# Eency_--_HM-10_v01.net
KiCad netlist of a schematic drawn in EAGLE
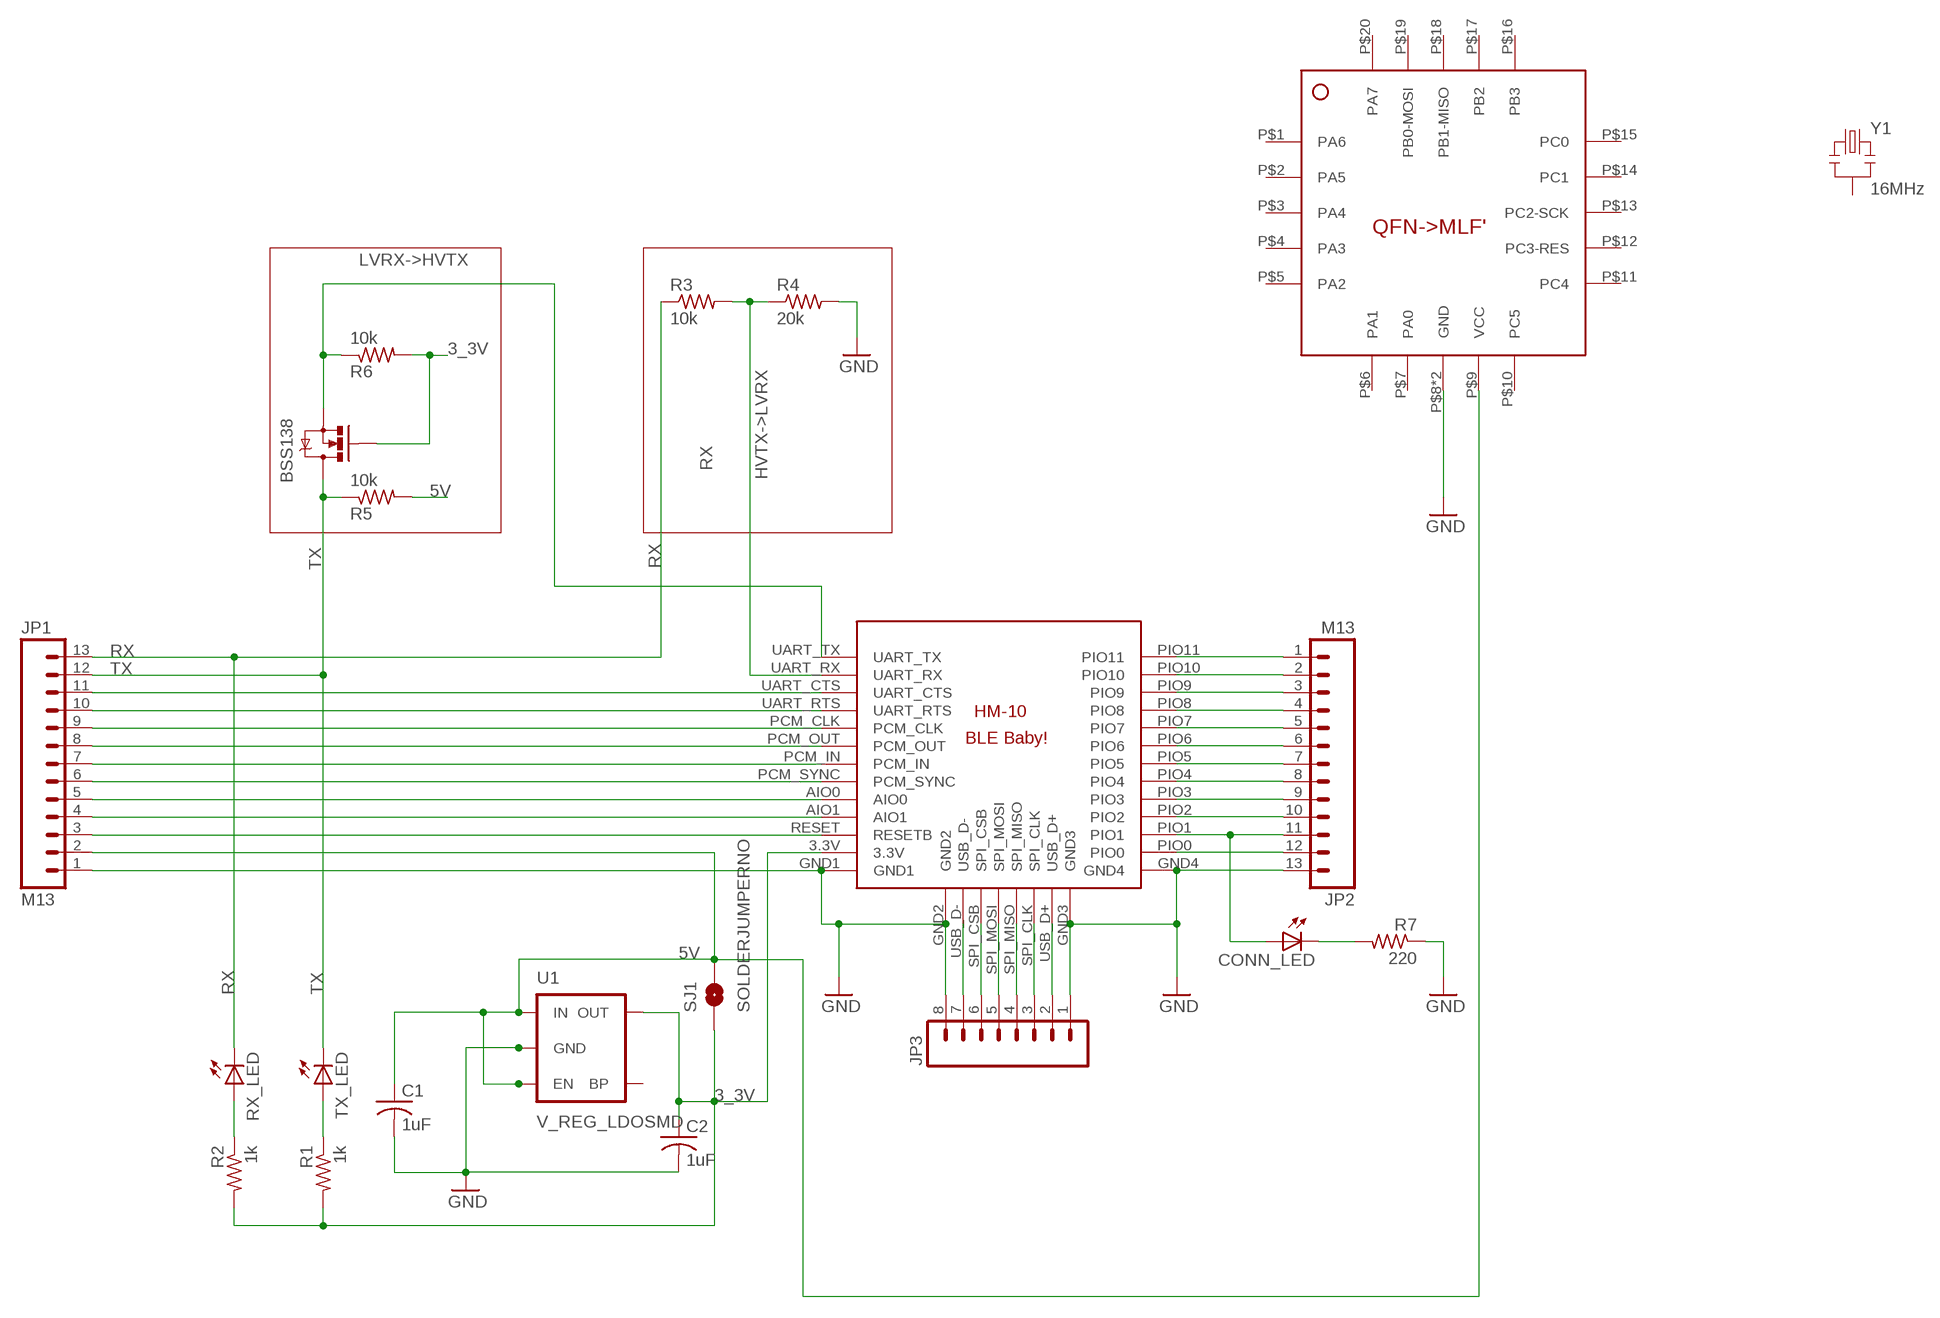
[diagram p0: schematic, sheet 1]

(export (version "E")
  (design (tool "Eeschema 10.0.6"))
  (components
    (comp (ref "BSS138")
      (value "MOSFET-NCHANNELSMD")
      (footprint "eagle-import:SOT23-3")
      (libsource (lib "eagle-import") (part "MOSFET-NCHANNELSMD"))
    )
    (comp (ref "C1")
      (value "1uF")
      (footprint "eagle-import:C0805K")
      (libsource (lib "eagle-import") (part "C-USC0805K"))
    )
    (comp (ref "C2")
      (value "1uF")
      (footprint "eagle-import:C0805K")
      (libsource (lib "eagle-import") (part "C-USC0805K"))
    )
    (comp (ref "CONN_LED")
      (value "LED0603")
      (footprint "eagle-import:LED-0603")
      (libsource (lib "eagle-import") (part "LED0603"))
    )
    (comp (ref "JP1")
      (value "M13")
      (footprint "eagle-import:1X13")
      (libsource (lib "eagle-import") (part "M13"))
    )
    (comp (ref "JP2")
      (value "M13")
      (footprint "eagle-import:1X13")
      (libsource (lib "eagle-import") (part "M13"))
    )
    (comp (ref "JP3")
      (value "M081X08")
      (footprint "eagle-import:1X08")
      (libsource (lib "eagle-import") (part "M081X08"))
    )
    (comp (ref "R1")
      (value "1k")
      (footprint "eagle-import:M0805")
      (libsource (lib "eagle-import") (part "R-US_M0805"))
    )
    (comp (ref "R2")
      (value "1k")
      (footprint "eagle-import:M0805")
      (libsource (lib "eagle-import") (part "R-US_M0805"))
    )
    (comp (ref "R3")
      (value "10k")
      (footprint "eagle-import:M0805")
      (libsource (lib "eagle-import") (part "R-US_M0805"))
    )
    (comp (ref "R4")
      (value "20k")
      (footprint "eagle-import:M0805")
      (libsource (lib "eagle-import") (part "R-US_M0805"))
    )
    (comp (ref "R5")
      (value "10k")
      (footprint "eagle-import:M0805")
      (libsource (lib "eagle-import") (part "R-US_M0805"))
    )
    (comp (ref "R6")
      (value "10k")
      (footprint "eagle-import:M0805")
      (libsource (lib "eagle-import") (part "R-US_M0805"))
    )
    (comp (ref "R7")
      (value "220")
      (footprint "eagle-import:M0805")
      (libsource (lib "eagle-import") (part "R-US_M0805"))
    )
    (comp (ref "RX_LED")
      (value "LED0603")
      (footprint "eagle-import:LED-0603")
      (libsource (lib "eagle-import") (part "LED0603"))
    )
    (comp (ref "SJ1")
      (value "SOLDERJUMPERNO")
      (footprint "eagle-import:SJ_2S-NO")
      (libsource (lib "eagle-import") (part "SOLDERJUMPERNO"))
    )
    (comp (ref "TX_LED")
      (value "LED0603")
      (footprint "eagle-import:LED-0603")
      (libsource (lib "eagle-import") (part "LED0603"))
    )
    (comp (ref "U$1")
      (value "BLE-HM-10")
      (footprint "eagle-import:BLE-HM-10")
      (libsource (lib "eagle-import") (part "BLE-HM-10"))
    )
    (comp (ref "U$4")
      (value "AVR-5_ATTINY1634")
      (footprint "eagle-import:AVR-5_MLF20_ATTINY13")
      (libsource (lib "eagle-import") (part "AVR-5_ATTINY1634"))
    )
    (comp (ref "U1")
      (value "V_REG_LDOSMD")
      (footprint "eagle-import:SOT23-5")
      (libsource (lib "eagle-import") (part "V_REG_LDOSMD"))
    )
    (comp (ref "Y1")
      (value "16MHz")
      (footprint "eagle-import:RESONATOR-SMD")
      (libsource (lib "eagle-import") (part "RESONATOR16MHZ"))
    )
  )
  (nets
    (net (code "1") (name "/3_3V") (class "Default")
      (node (ref "BSS138") (pin "1") (pinfunction "G_1") (pintype "passive"))
      (node (ref "C2") (pin "1") (pinfunction "1_1") (pintype "passive"))
      (node (ref "R1") (pin "2") (pinfunction "2_2") (pintype "passive"))
      (node (ref "R2") (pin "2") (pinfunction "2_2") (pintype "passive"))
      (node (ref "R6") (pin "2") (pinfunction "2_2") (pintype "passive"))
      (node (ref "SJ1") (pin "1") (pinfunction "1_1") (pintype "passive"))
      (node (ref "U$1") (pin "3.3V") (pinfunction "3.3V_3.3V") (pintype "bidirectional"))
      (node (ref "U1") (pin "5") (pinfunction "OUT_5") (pintype "passive"))
    )
    (net (code "2") (name "/5V") (class "Default")
      (node (ref "C1") (pin "1") (pinfunction "1_1") (pintype "passive"))
      (node (ref "JP1") (pin "2") (pinfunction "2_2") (pintype "passive"))
      (node (ref "R5") (pin "2") (pinfunction "2_2") (pintype "passive"))
      (node (ref "SJ1") (pin "2") (pinfunction "2_2") (pintype "passive"))
      (node (ref "U$4") (pin "P$9") (pinfunction "VCC_P$9") (pintype "bidirectional"))
      (node (ref "U1") (pin "1") (pinfunction "IN_1") (pintype "input"))
      (node (ref "U1") (pin "3") (pinfunction "EN_3") (pintype "input"))
    )
    (net (code "3") (name "/HVTX->LVRX") (class "Default")
      (node (ref "R3") (pin "2") (pinfunction "2_2") (pintype "passive"))
      (node (ref "R4") (pin "1") (pinfunction "1_1") (pintype "passive"))
      (node (ref "U$1") (pin "UART_RX") (pinfunction "UART_RX_UART_RX") (pintype "bidirectional"))
    )
    (net (code "4") (name "/LVRX->HVTX") (class "Default")
      (node (ref "BSS138") (pin "2") (pinfunction "S_2") (pintype "passive"))
      (node (ref "R6") (pin "1") (pinfunction "1_1") (pintype "passive"))
      (node (ref "U$1") (pin "UART_TX") (pinfunction "UART_TX_UART_TX") (pintype "bidirectional"))
    )
    (net (code "5") (name "/RX") (class "Default")
      (node (ref "JP1") (pin "13") (pinfunction "13_13") (pintype "passive"))
      (node (ref "R3") (pin "1") (pinfunction "1_1") (pintype "passive"))
      (node (ref "RX_LED") (pin "C") (pinfunction "C_C") (pintype "passive"))
    )
    (net (code "6") (name "/TX") (class "Default")
      (node (ref "BSS138") (pin "3") (pinfunction "D_3") (pintype "passive"))
      (node (ref "JP1") (pin "12") (pinfunction "12_12") (pintype "passive"))
      (node (ref "R5") (pin "1") (pinfunction "1_1") (pintype "passive"))
      (node (ref "TX_LED") (pin "C") (pinfunction "C_C") (pintype "passive"))
    )
    (net (code "7") (name "GND") (class "Default")
      (node (ref "C1") (pin "2") (pinfunction "2_2") (pintype "passive"))
      (node (ref "C2") (pin "2") (pinfunction "2_2") (pintype "passive"))
      (node (ref "JP1") (pin "1") (pinfunction "1_1") (pintype "passive"))
      (node (ref "JP2") (pin "13") (pinfunction "13_13") (pintype "passive"))
      (node (ref "JP3") (pin "1") (pinfunction "1_1") (pintype "passive"))
      (node (ref "JP3") (pin "8") (pinfunction "8_8") (pintype "passive"))
      (node (ref "R4") (pin "2") (pinfunction "2_2") (pintype "passive"))
      (node (ref "R7") (pin "1") (pinfunction "1_1") (pintype "passive"))
      (node (ref "U$1") (pin "GND1") (pinfunction "GND1_GND1") (pintype "bidirectional"))
      (node (ref "U$1") (pin "GND2") (pinfunction "GND2_GND2") (pintype "bidirectional"))
      (node (ref "U$1") (pin "GND3") (pinfunction "GND3_GND3") (pintype "bidirectional"))
      (node (ref "U$1") (pin "GND4") (pinfunction "GND4_GND4") (pintype "bidirectional"))
      (node (ref "U$4") (pin "P$21") (pinfunction "GND_P$21") (pintype "bidirectional"))
      (node (ref "U$4") (pin "P$8") (pinfunction "GND_P$8") (pintype "bidirectional"))
      (node (ref "U1") (pin "2") (pinfunction "GND_2") (pintype "input"))
    )
    (net (code "8") (name "Net-(CONN_LED-PadA)") (class "Default")
      (node (ref "CONN_LED") (pin "A") (pinfunction "A_A") (pintype "passive"))
      (node (ref "JP2") (pin "11") (pinfunction "11_11") (pintype "passive"))
      (node (ref "U$1") (pin "PIO1") (pinfunction "PIO1_PIO1") (pintype "bidirectional"))
    )
    (net (code "9") (name "Net-(CONN_LED-PadC)") (class "Default")
      (node (ref "CONN_LED") (pin "C") (pinfunction "C_C") (pintype "passive"))
      (node (ref "R7") (pin "2") (pinfunction "2_2") (pintype "passive"))
    )
    (net (code "10") (name "Net-(JP1-Pad4)") (class "Default")
      (node (ref "JP1") (pin "4") (pinfunction "4_4") (pintype "passive"))
      (node (ref "U$1") (pin "AIO1") (pinfunction "AIO1_AIO1") (pintype "bidirectional"))
    )
    (net (code "11") (name "Net-(JP1-Pad5)") (class "Default")
      (node (ref "JP1") (pin "5") (pinfunction "5_5") (pintype "passive"))
      (node (ref "U$1") (pin "AIO0") (pinfunction "AIO0_AIO0") (pintype "bidirectional"))
    )
    (net (code "12") (name "Net-(JP1-Pad6)") (class "Default")
      (node (ref "JP1") (pin "6") (pinfunction "6_6") (pintype "passive"))
      (node (ref "U$1") (pin "PCM_SYNC") (pinfunction "PCM_SYNC_PCM_SYNC") (pintype "bidirectional"))
    )
    (net (code "13") (name "Net-(JP1-Pad7)") (class "Default")
      (node (ref "JP1") (pin "7") (pinfunction "7_7") (pintype "passive"))
      (node (ref "U$1") (pin "PCM_IN") (pinfunction "PCM_IN_PCM_IN") (pintype "bidirectional"))
    )
    (net (code "14") (name "Net-(JP1-Pad8)") (class "Default")
      (node (ref "JP1") (pin "8") (pinfunction "8_8") (pintype "passive"))
      (node (ref "U$1") (pin "PCM_OUT") (pinfunction "PCM_OUT_PCM_OUT") (pintype "bidirectional"))
    )
    (net (code "15") (name "Net-(JP1-Pad9)") (class "Default")
      (node (ref "JP1") (pin "9") (pinfunction "9_9") (pintype "passive"))
      (node (ref "U$1") (pin "PCM_CLK") (pinfunction "PCM_CLK_PCM_CLK") (pintype "bidirectional"))
    )
    (net (code "16") (name "Net-(JP1-Pad10)") (class "Default")
      (node (ref "JP1") (pin "10") (pinfunction "10_10") (pintype "passive"))
      (node (ref "U$1") (pin "UART_RTS") (pinfunction "UART_RTS_UART_RTS") (pintype "bidirectional"))
    )
    (net (code "17") (name "Net-(JP1-Pad11)") (class "Default")
      (node (ref "JP1") (pin "11") (pinfunction "11_11") (pintype "passive"))
      (node (ref "U$1") (pin "UART_CTS") (pinfunction "UART_CTS_UART_CTS") (pintype "bidirectional"))
    )
    (net (code "18") (name "Net-(JP2-Pad1)") (class "Default")
      (node (ref "JP2") (pin "1") (pinfunction "1_1") (pintype "passive"))
      (node (ref "U$1") (pin "PIO11") (pinfunction "PIO11_PIO11") (pintype "bidirectional"))
    )
    (net (code "19") (name "Net-(JP2-Pad2)") (class "Default")
      (node (ref "JP2") (pin "2") (pinfunction "2_2") (pintype "passive"))
      (node (ref "U$1") (pin "PIO10") (pinfunction "PIO10_PIO10") (pintype "bidirectional"))
    )
    (net (code "20") (name "Net-(JP2-Pad3)") (class "Default")
      (node (ref "JP2") (pin "3") (pinfunction "3_3") (pintype "passive"))
      (node (ref "U$1") (pin "PIO9") (pinfunction "PIO9_PIO9") (pintype "bidirectional"))
    )
    (net (code "21") (name "Net-(JP2-Pad4)") (class "Default")
      (node (ref "JP2") (pin "4") (pinfunction "4_4") (pintype "passive"))
      (node (ref "U$1") (pin "PIO8") (pinfunction "PIO8_PIO8") (pintype "bidirectional"))
    )
    (net (code "22") (name "Net-(JP2-Pad5)") (class "Default")
      (node (ref "JP2") (pin "5") (pinfunction "5_5") (pintype "passive"))
      (node (ref "U$1") (pin "PIO7") (pinfunction "PIO7_PIO7") (pintype "bidirectional"))
    )
    (net (code "23") (name "Net-(JP2-Pad6)") (class "Default")
      (node (ref "JP2") (pin "6") (pinfunction "6_6") (pintype "passive"))
      (node (ref "U$1") (pin "PIO6") (pinfunction "PIO6_PIO6") (pintype "bidirectional"))
    )
    (net (code "24") (name "Net-(JP2-Pad7)") (class "Default")
      (node (ref "JP2") (pin "7") (pinfunction "7_7") (pintype "passive"))
      (node (ref "U$1") (pin "PIO5") (pinfunction "PIO5_PIO5") (pintype "bidirectional"))
    )
    (net (code "25") (name "Net-(JP2-Pad8)") (class "Default")
      (node (ref "JP2") (pin "8") (pinfunction "8_8") (pintype "passive"))
      (node (ref "U$1") (pin "PIO4") (pinfunction "PIO4_PIO4") (pintype "bidirectional"))
    )
    (net (code "26") (name "Net-(JP2-Pad9)") (class "Default")
      (node (ref "JP2") (pin "9") (pinfunction "9_9") (pintype "passive"))
      (node (ref "U$1") (pin "PIO3") (pinfunction "PIO3_PIO3") (pintype "bidirectional"))
    )
    (net (code "27") (name "Net-(JP2-Pad10)") (class "Default")
      (node (ref "JP2") (pin "10") (pinfunction "10_10") (pintype "passive"))
      (node (ref "U$1") (pin "PIO2") (pinfunction "PIO2_PIO2") (pintype "bidirectional"))
    )
    (net (code "28") (name "Net-(JP2-Pad12)") (class "Default")
      (node (ref "JP2") (pin "12") (pinfunction "12_12") (pintype "passive"))
      (node (ref "U$1") (pin "PIO0") (pinfunction "PIO0_PIO0") (pintype "bidirectional"))
    )
    (net (code "29") (name "Net-(JP3-Pad2)") (class "Default")
      (node (ref "JP3") (pin "2") (pinfunction "2_2") (pintype "passive"))
      (node (ref "U$1") (pin "USB_D+") (pinfunction "USB_D+_USB_D+") (pintype "bidirectional"))
    )
    (net (code "30") (name "Net-(JP3-Pad3)") (class "Default")
      (node (ref "JP3") (pin "3") (pinfunction "3_3") (pintype "passive"))
      (node (ref "U$1") (pin "SPI_CLK") (pinfunction "SPI_CLK_SPI_CLK") (pintype "bidirectional"))
    )
    (net (code "31") (name "Net-(JP3-Pad4)") (class "Default")
      (node (ref "JP3") (pin "4") (pinfunction "4_4") (pintype "passive"))
      (node (ref "U$1") (pin "SPI_MISO") (pinfunction "SPI_MISO_SPI_MISO") (pintype "bidirectional"))
    )
    (net (code "32") (name "Net-(JP3-Pad5)") (class "Default")
      (node (ref "JP3") (pin "5") (pinfunction "5_5") (pintype "passive"))
      (node (ref "U$1") (pin "SPI_MOSI") (pinfunction "SPI_MOSI_SPI_MOSI") (pintype "bidirectional"))
    )
    (net (code "33") (name "Net-(JP3-Pad6)") (class "Default")
      (node (ref "JP3") (pin "6") (pinfunction "6_6") (pintype "passive"))
      (node (ref "U$1") (pin "SPI_CSB") (pinfunction "SPI_CSB_SPI_CSB") (pintype "bidirectional"))
    )
    (net (code "34") (name "Net-(JP3-Pad7)") (class "Default")
      (node (ref "JP3") (pin "7") (pinfunction "7_7") (pintype "passive"))
      (node (ref "U$1") (pin "USB_D-") (pinfunction "USB_D-_USB_D-") (pintype "bidirectional"))
    )
    (net (code "35") (name "Net-(R1-Pad1)") (class "Default")
      (node (ref "R1") (pin "1") (pinfunction "1_1") (pintype "passive"))
      (node (ref "TX_LED") (pin "A") (pinfunction "A_A") (pintype "passive"))
    )
    (net (code "36") (name "Net-(R2-Pad1)") (class "Default")
      (node (ref "R2") (pin "1") (pinfunction "1_1") (pintype "passive"))
      (node (ref "RX_LED") (pin "A") (pinfunction "A_A") (pintype "passive"))
    )
    (net (code "37") (name "Net-(U$1-RESETB)") (class "Default")
      (node (ref "JP1") (pin "3") (pinfunction "3_3") (pintype "passive"))
      (node (ref "U$1") (pin "RESET") (pinfunction "RESETB_RESET") (pintype "bidirectional"))
    )
    (net (code "38") (name "unconnected-(U$4-PA0-PadP$7)") (class "Default")
      (node (ref "U$4") (pin "P$7") (pinfunction "PA0_P$7") (pintype "bidirectional"))
    )
    (net (code "39") (name "unconnected-(U$4-PA1-PadP$6)") (class "Default")
      (node (ref "U$4") (pin "P$6") (pinfunction "PA1_P$6") (pintype "bidirectional"))
    )
    (net (code "40") (name "unconnected-(U$4-PA2-PadP$5)") (class "Default")
      (node (ref "U$4") (pin "P$5") (pinfunction "PA2_P$5") (pintype "bidirectional"))
    )
    (net (code "41") (name "unconnected-(U$4-PA3-PadP$4)") (class "Default")
      (node (ref "U$4") (pin "P$4") (pinfunction "PA3_P$4") (pintype "bidirectional"))
    )
    (net (code "42") (name "unconnected-(U$4-PA4-PadP$3)") (class "Default")
      (node (ref "U$4") (pin "P$3") (pinfunction "PA4_P$3") (pintype "bidirectional"))
    )
    (net (code "43") (name "unconnected-(U$4-PA5-PadP$2)") (class "Default")
      (node (ref "U$4") (pin "P$2") (pinfunction "PA5_P$2") (pintype "bidirectional"))
    )
    (net (code "44") (name "unconnected-(U$4-PA6-PadP$1)") (class "Default")
      (node (ref "U$4") (pin "P$1") (pinfunction "PA6_P$1") (pintype "bidirectional"))
    )
    (net (code "45") (name "unconnected-(U$4-PA7-PadP$20)") (class "Default")
      (node (ref "U$4") (pin "P$20") (pinfunction "PA7_P$20") (pintype "bidirectional"))
    )
    (net (code "46") (name "unconnected-(U$4-PB0-MOSI-PadP$19)") (class "Default")
      (node (ref "U$4") (pin "P$19") (pinfunction "PB0-MOSI_P$19") (pintype "bidirectional"))
    )
    (net (code "47") (name "unconnected-(U$4-PB1-MISO-PadP$18)") (class "Default")
      (node (ref "U$4") (pin "P$18") (pinfunction "PB1-MISO_P$18") (pintype "bidirectional"))
    )
    (net (code "48") (name "unconnected-(U$4-PB2-PadP$17)") (class "Default")
      (node (ref "U$4") (pin "P$17") (pinfunction "PB2_P$17") (pintype "bidirectional"))
    )
    (net (code "49") (name "unconnected-(U$4-PB3-PadP$16)") (class "Default")
      (node (ref "U$4") (pin "P$16") (pinfunction "PB3_P$16") (pintype "bidirectional"))
    )
    (net (code "50") (name "unconnected-(U$4-PC0-PadP$15)") (class "Default")
      (node (ref "U$4") (pin "P$15") (pinfunction "PC0_P$15") (pintype "bidirectional"))
    )
    (net (code "51") (name "unconnected-(U$4-PC1-PadP$14)") (class "Default")
      (node (ref "U$4") (pin "P$14") (pinfunction "PC1_P$14") (pintype "bidirectional"))
    )
    (net (code "52") (name "unconnected-(U$4-PC2-SCK-PadP$13)") (class "Default")
      (node (ref "U$4") (pin "P$13") (pinfunction "PC2-SCK_P$13") (pintype "bidirectional"))
    )
    (net (code "53") (name "unconnected-(U$4-PC3-RES-PadP$12)") (class "Default")
      (node (ref "U$4") (pin "P$12") (pinfunction "PC3-RES_P$12") (pintype "bidirectional"))
    )
    (net (code "54") (name "unconnected-(U$4-PC4-PadP$11)") (class "Default")
      (node (ref "U$4") (pin "P$11") (pinfunction "PC4_P$11") (pintype "bidirectional"))
    )
    (net (code "55") (name "unconnected-(U$4-PC5-PadP$10)") (class "Default")
      (node (ref "U$4") (pin "P$10") (pinfunction "PC5_P$10") (pintype "bidirectional"))
    )
    (net (code "56") (name "unconnected-(U1-BP-Pad4)") (class "Default")
      (node (ref "U1") (pin "4") (pinfunction "BP_4") (pintype "input"))
    )
    (net (code "57") (name "unconnected-(Y1-Pad1)") (class "Default")
      (node (ref "Y1") (pin "1") (pinfunction "1_1") (pintype "passive"))
    )
    (net (code "58") (name "unconnected-(Y1-Pad2)") (class "Default")
      (node (ref "Y1") (pin "2") (pinfunction "2_2") (pintype "passive"))
    )
    (net (code "59") (name "unconnected-(Y1-Pad3)") (class "Default")
      (node (ref "Y1") (pin "3") (pinfunction "3_3") (pintype "passive"))
    )
  )
)
